# WicinskiPI.net
KiCad netlist of a schematic drawn in EAGLE
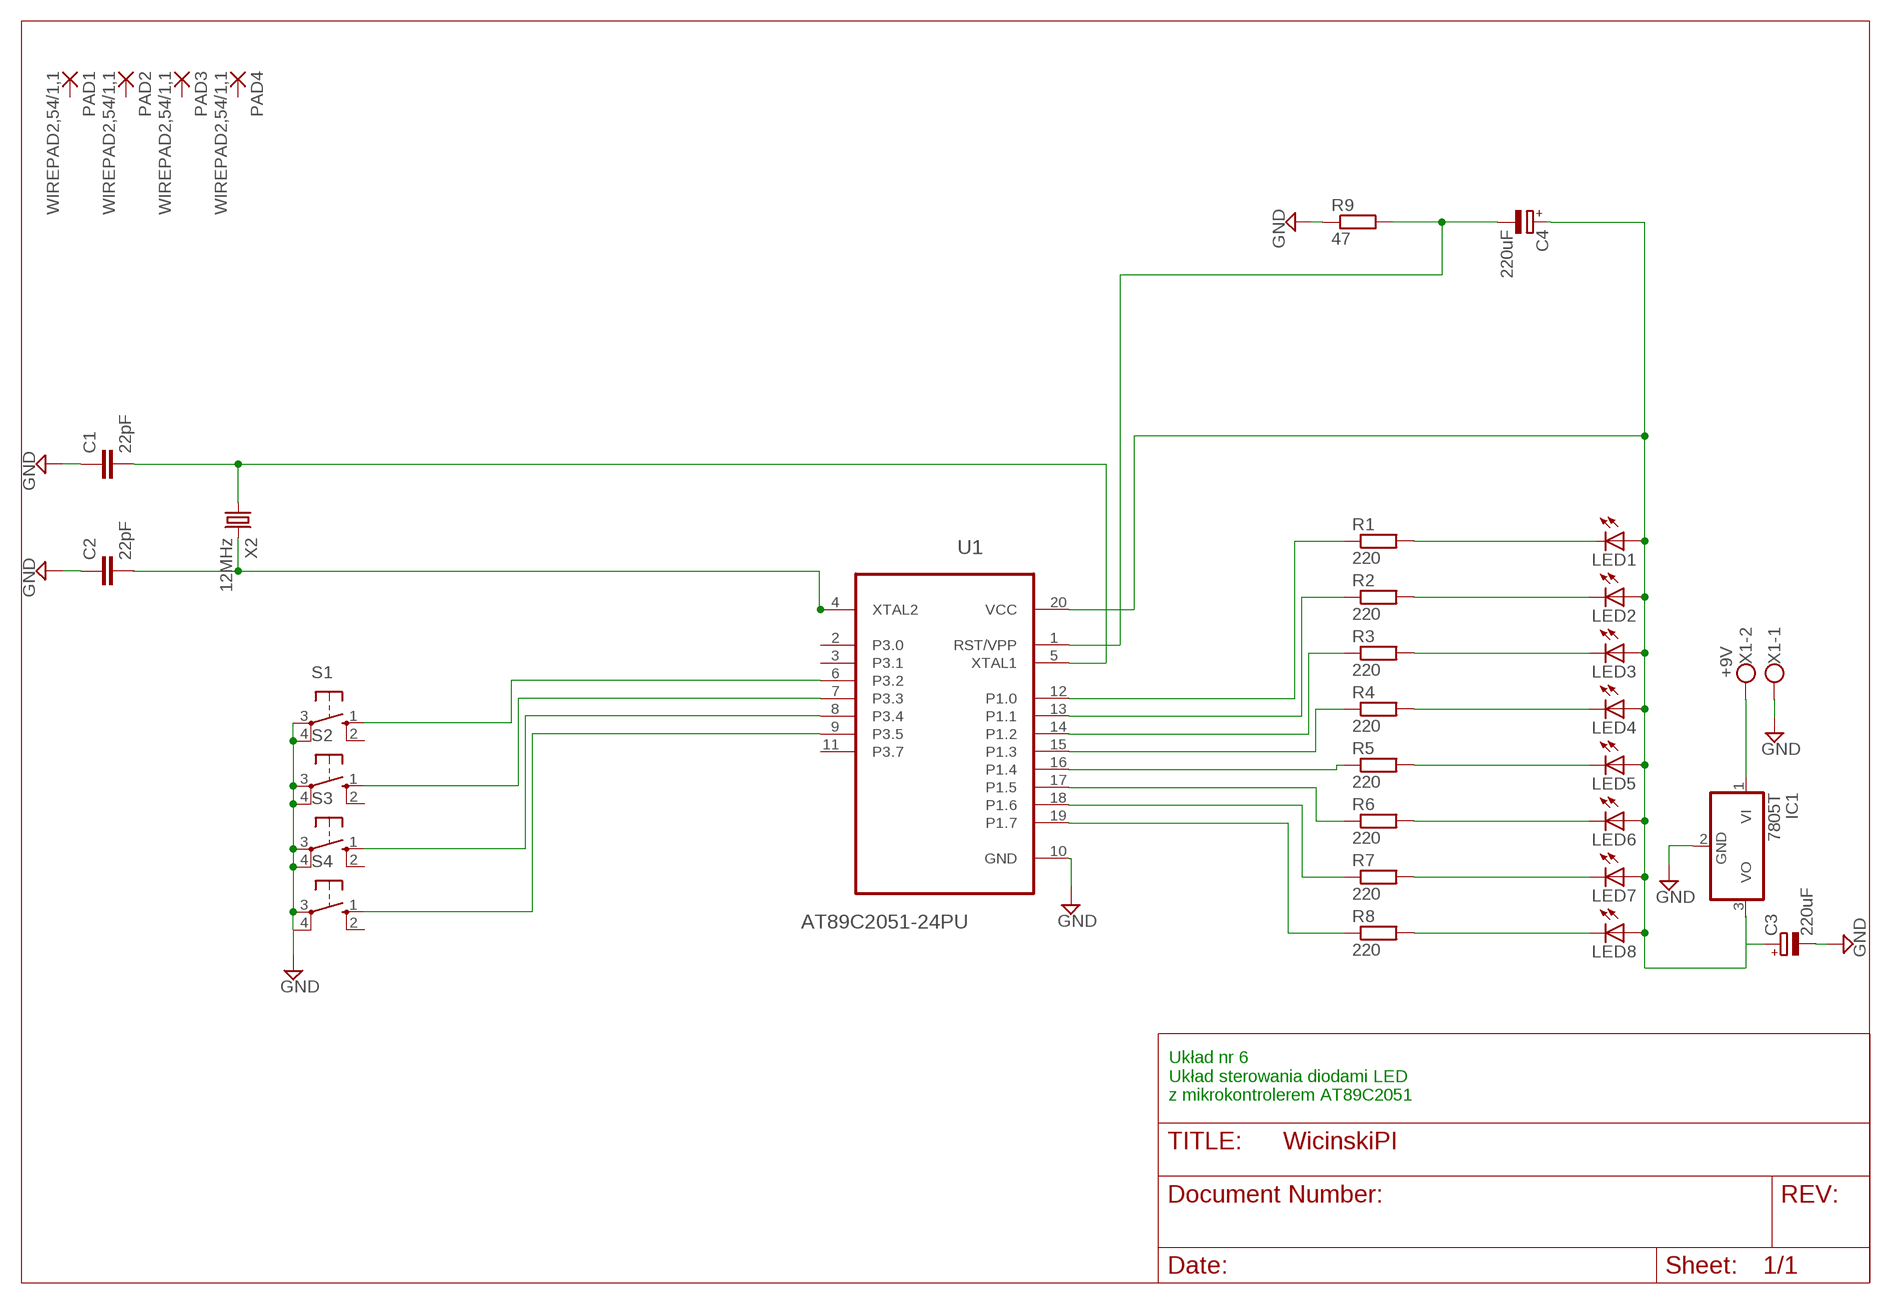
[diagram p0: schematic, sheet 1]

(export (version "E")
  (design (tool "Eeschema 10.0.6"))
  (components
    (comp (ref "C1")
      (value "22pF")
      (footprint "eagle-import:C1206")
      (libsource (lib "eagle-import") (part "C-EUC1206"))
    )
    (comp (ref "C2")
      (value "22pF")
      (footprint "eagle-import:C1206")
      (libsource (lib "eagle-import") (part "C-EUC1206"))
    )
    (comp (ref "C3")
      (value "220uF")
      (footprint "eagle-import:E3,5-8")
      (libsource (lib "eagle-import") (part "CPOL-EUE3.5-8"))
    )
    (comp (ref "C4")
      (value "220uF")
      (footprint "eagle-import:E3,5-8")
      (libsource (lib "eagle-import") (part "CPOL-EUE3.5-8"))
    )
    (comp (ref "IC1")
      (value "7805T")
      (footprint "eagle-import:TO220H")
      (libsource (lib "eagle-import") (part "78T05"))
    )
    (comp (ref "LED1")
      (value "LED3MM")
      (footprint "eagle-import:LED3MM")
      (libsource (lib "eagle-import") (part "LED3MM"))
    )
    (comp (ref "LED2")
      (value "LED3MM")
      (footprint "eagle-import:LED3MM")
      (libsource (lib "eagle-import") (part "LED3MM"))
    )
    (comp (ref "LED3")
      (value "LED3MM")
      (footprint "eagle-import:LED3MM")
      (libsource (lib "eagle-import") (part "LED3MM"))
    )
    (comp (ref "LED4")
      (value "LED3MM")
      (footprint "eagle-import:LED3MM")
      (libsource (lib "eagle-import") (part "LED3MM"))
    )
    (comp (ref "LED5")
      (value "LED3MM")
      (footprint "eagle-import:LED3MM")
      (libsource (lib "eagle-import") (part "LED3MM"))
    )
    (comp (ref "LED6")
      (value "LED3MM")
      (footprint "eagle-import:LED3MM")
      (libsource (lib "eagle-import") (part "LED3MM"))
    )
    (comp (ref "LED7")
      (value "LED3MM")
      (footprint "eagle-import:LED3MM")
      (libsource (lib "eagle-import") (part "LED3MM"))
    )
    (comp (ref "LED8")
      (value "LED3MM")
      (footprint "eagle-import:LED3MM")
      (libsource (lib "eagle-import") (part "LED3MM"))
    )
    (comp (ref "PAD1")
      (value "WIREPAD2,54/1,1")
      (footprint "eagle-import:2,54_1,1")
      (libsource (lib "eagle-import") (part "WIREPAD2,54/1,1"))
    )
    (comp (ref "PAD2")
      (value "WIREPAD2,54/1,1")
      (footprint "eagle-import:2,54_1,1")
      (libsource (lib "eagle-import") (part "WIREPAD2,54/1,1"))
    )
    (comp (ref "PAD3")
      (value "WIREPAD2,54/1,1")
      (footprint "eagle-import:2,54_1,1")
      (libsource (lib "eagle-import") (part "WIREPAD2,54/1,1"))
    )
    (comp (ref "PAD4")
      (value "WIREPAD2,54/1,1")
      (footprint "eagle-import:2,54_1,1")
      (libsource (lib "eagle-import") (part "WIREPAD2,54/1,1"))
    )
    (comp (ref "R1")
      (value "220")
      (footprint "eagle-import:R2012")
      (libsource (lib "eagle-import") (part "R-EU_R2012"))
    )
    (comp (ref "R2")
      (value "220")
      (footprint "eagle-import:R2012")
      (libsource (lib "eagle-import") (part "R-EU_R2012"))
    )
    (comp (ref "R3")
      (value "220")
      (footprint "eagle-import:R2012")
      (libsource (lib "eagle-import") (part "R-EU_R2012"))
    )
    (comp (ref "R4")
      (value "220")
      (footprint "eagle-import:R2012")
      (libsource (lib "eagle-import") (part "R-EU_R2012"))
    )
    (comp (ref "R5")
      (value "220")
      (footprint "eagle-import:R2012")
      (libsource (lib "eagle-import") (part "R-EU_R2012"))
    )
    (comp (ref "R6")
      (value "220")
      (footprint "eagle-import:R2012")
      (libsource (lib "eagle-import") (part "R-EU_R2012"))
    )
    (comp (ref "R7")
      (value "220")
      (footprint "eagle-import:R2012")
      (libsource (lib "eagle-import") (part "R-EU_R2012"))
    )
    (comp (ref "R8")
      (value "220")
      (footprint "eagle-import:R2012")
      (libsource (lib "eagle-import") (part "R-EU_R2012"))
    )
    (comp (ref "R9")
      (value "47")
      (footprint "eagle-import:R2012")
      (libsource (lib "eagle-import") (part "R-EU_R2012"))
    )
    (comp (ref "S1")
      (value "10-XX")
      (footprint "eagle-import:B3F-10XX")
      (fields (field (name "MPN") "B3F-1000"))
      (libsource (lib "eagle-import") (part "10-XX"))
    )
    (comp (ref "S2")
      (value "10-XX")
      (footprint "eagle-import:B3F-10XX")
      (fields (field (name "MPN") "B3F-1000"))
      (libsource (lib "eagle-import") (part "10-XX"))
    )
    (comp (ref "S3")
      (value "10-XX")
      (footprint "eagle-import:B3F-10XX")
      (fields (field (name "MPN") "B3F-1000"))
      (libsource (lib "eagle-import") (part "10-XX"))
    )
    (comp (ref "S4")
      (value "10-XX")
      (footprint "eagle-import:B3F-10XX")
      (fields (field (name "MPN") "B3F-1000"))
      (libsource (lib "eagle-import") (part "10-XX"))
    )
    (comp (ref "U1")
      (value "AT89C2051-24PU")
      (footprint "eagle-import:DIP254P762X533-20")
      (fields (field (name "MF") "Microchip"))
      (libsource (lib "eagle-import") (part "AT89C2051-24PU"))
    )
    (comp (ref "X1")
      (value "+9V")
      (footprint "eagle-import:W237-102")
      (fields (field (name "MPN") "237-102"))
      (libsource (lib "eagle-import") (part "W237-102"))
    )
    (comp (ref "X2")
      (value "12MHz")
      (footprint "eagle-import:HC49")
      (libsource (lib "eagle-import") (part "CRYSTALS-NOGND-HC49"))
    )
  )
  (nets
    (net (code "1") (name "GND") (class "Default")
      (node (ref "C1") (pin "1") (pinfunction "1_1") (pintype "passive"))
      (node (ref "C2") (pin "1") (pinfunction "1_1") (pintype "passive"))
      (node (ref "C3") (pin "-") (pinfunction "-_-") (pintype "passive"))
      (node (ref "IC1") (pin "2") (pinfunction "GND_2") (pintype "passive"))
      (node (ref "R9") (pin "1") (pinfunction "1_1") (pintype "passive"))
      (node (ref "S1") (pin "3") (pinfunction "P_3") (pintype "passive"))
      (node (ref "S1") (pin "4") (pinfunction "P1_4") (pintype "passive"))
      (node (ref "S2") (pin "3") (pinfunction "P_3") (pintype "passive"))
      (node (ref "S2") (pin "4") (pinfunction "P1_4") (pintype "passive"))
      (node (ref "S3") (pin "3") (pinfunction "P_3") (pintype "passive"))
      (node (ref "S3") (pin "4") (pinfunction "P1_4") (pintype "passive"))
      (node (ref "S4") (pin "3") (pinfunction "P_3") (pintype "passive"))
      (node (ref "S4") (pin "4") (pinfunction "P1_4") (pintype "passive"))
      (node (ref "U1") (pin "10") (pinfunction "GND_10") (pintype "passive"))
      (node (ref "X1") (pin "1") (pinfunction "KL_1") (pintype "passive"))
    )
    (net (code "2") (name "Net-(IC1-VI)") (class "Default")
      (node (ref "IC1") (pin "1") (pinfunction "VI_1") (pintype "input"))
      (node (ref "X1") (pin "2") (pinfunction "KL_2") (pintype "passive"))
    )
    (net (code "3") (name "Net-(IC1-VO)") (class "Default")
      (node (ref "C3") (pin "+") (pinfunction "+_+") (pintype "passive"))
      (node (ref "C4") (pin "+") (pinfunction "+_+") (pintype "passive"))
      (node (ref "IC1") (pin "3") (pinfunction "VO_3") (pintype "passive"))
      (node (ref "LED1") (pin "A") (pinfunction "A_A") (pintype "passive"))
      (node (ref "LED2") (pin "A") (pinfunction "A_A") (pintype "passive"))
      (node (ref "LED3") (pin "A") (pinfunction "A_A") (pintype "passive"))
      (node (ref "LED4") (pin "A") (pinfunction "A_A") (pintype "passive"))
      (node (ref "LED5") (pin "A") (pinfunction "A_A") (pintype "passive"))
      (node (ref "LED6") (pin "A") (pinfunction "A_A") (pintype "passive"))
      (node (ref "LED7") (pin "A") (pinfunction "A_A") (pintype "passive"))
      (node (ref "LED8") (pin "A") (pinfunction "A_A") (pintype "passive"))
      (node (ref "U1") (pin "20") (pinfunction "VCC_20") (pintype "power_in"))
    )
    (net (code "4") (name "Net-(LED1-C)") (class "Default")
      (node (ref "LED1") (pin "K") (pinfunction "C_K") (pintype "passive"))
      (node (ref "R1") (pin "2") (pinfunction "2_2") (pintype "passive"))
    )
    (net (code "5") (name "Net-(LED2-C)") (class "Default")
      (node (ref "LED2") (pin "K") (pinfunction "C_K") (pintype "passive"))
      (node (ref "R2") (pin "2") (pinfunction "2_2") (pintype "passive"))
    )
    (net (code "6") (name "Net-(LED3-C)") (class "Default")
      (node (ref "LED3") (pin "K") (pinfunction "C_K") (pintype "passive"))
      (node (ref "R3") (pin "2") (pinfunction "2_2") (pintype "passive"))
    )
    (net (code "7") (name "Net-(LED4-C)") (class "Default")
      (node (ref "LED4") (pin "K") (pinfunction "C_K") (pintype "passive"))
      (node (ref "R4") (pin "2") (pinfunction "2_2") (pintype "passive"))
    )
    (net (code "8") (name "Net-(LED5-C)") (class "Default")
      (node (ref "LED5") (pin "K") (pinfunction "C_K") (pintype "passive"))
      (node (ref "R5") (pin "2") (pinfunction "2_2") (pintype "passive"))
    )
    (net (code "9") (name "Net-(LED6-C)") (class "Default")
      (node (ref "LED6") (pin "K") (pinfunction "C_K") (pintype "passive"))
      (node (ref "R6") (pin "2") (pinfunction "2_2") (pintype "passive"))
    )
    (net (code "10") (name "Net-(LED7-C)") (class "Default")
      (node (ref "LED7") (pin "K") (pinfunction "C_K") (pintype "passive"))
      (node (ref "R7") (pin "2") (pinfunction "2_2") (pintype "passive"))
    )
    (net (code "11") (name "Net-(LED8-C)") (class "Default")
      (node (ref "LED8") (pin "K") (pinfunction "C_K") (pintype "passive"))
      (node (ref "R8") (pin "2") (pinfunction "2_2") (pintype "passive"))
    )
    (net (code "12") (name "Net-(S1-S)") (class "Default")
      (node (ref "S1") (pin "1") (pinfunction "S_1") (pintype "passive"))
      (node (ref "U1") (pin "6") (pinfunction "P3.2_6") (pintype "bidirectional"))
    )
    (net (code "13") (name "Net-(S2-S)") (class "Default")
      (node (ref "S2") (pin "1") (pinfunction "S_1") (pintype "passive"))
      (node (ref "U1") (pin "7") (pinfunction "P3.3_7") (pintype "bidirectional"))
    )
    (net (code "14") (name "Net-(S3-S)") (class "Default")
      (node (ref "S3") (pin "1") (pinfunction "S_1") (pintype "passive"))
      (node (ref "U1") (pin "8") (pinfunction "P3.4_8") (pintype "bidirectional"))
    )
    (net (code "15") (name "Net-(S4-S)") (class "Default")
      (node (ref "S4") (pin "1") (pinfunction "S_1") (pintype "passive"))
      (node (ref "U1") (pin "9") (pinfunction "P3.5_9") (pintype "bidirectional"))
    )
    (net (code "16") (name "Net-(U1-P1.0)") (class "Default")
      (node (ref "R1") (pin "1") (pinfunction "1_1") (pintype "passive"))
      (node (ref "U1") (pin "12") (pinfunction "P1.0_12") (pintype "bidirectional"))
    )
    (net (code "17") (name "Net-(U1-P1.1)") (class "Default")
      (node (ref "R2") (pin "1") (pinfunction "1_1") (pintype "passive"))
      (node (ref "U1") (pin "13") (pinfunction "P1.1_13") (pintype "bidirectional"))
    )
    (net (code "18") (name "Net-(U1-P1.2)") (class "Default")
      (node (ref "R3") (pin "1") (pinfunction "1_1") (pintype "passive"))
      (node (ref "U1") (pin "14") (pinfunction "P1.2_14") (pintype "bidirectional"))
    )
    (net (code "19") (name "Net-(U1-P1.3)") (class "Default")
      (node (ref "R4") (pin "1") (pinfunction "1_1") (pintype "passive"))
      (node (ref "U1") (pin "15") (pinfunction "P1.3_15") (pintype "bidirectional"))
    )
    (net (code "20") (name "Net-(U1-P1.4)") (class "Default")
      (node (ref "R5") (pin "1") (pinfunction "1_1") (pintype "passive"))
      (node (ref "U1") (pin "16") (pinfunction "P1.4_16") (pintype "bidirectional"))
    )
    (net (code "21") (name "Net-(U1-P1.5)") (class "Default")
      (node (ref "R6") (pin "1") (pinfunction "1_1") (pintype "passive"))
      (node (ref "U1") (pin "17") (pinfunction "P1.5_17") (pintype "bidirectional"))
    )
    (net (code "22") (name "Net-(U1-P1.6)") (class "Default")
      (node (ref "R7") (pin "1") (pinfunction "1_1") (pintype "passive"))
      (node (ref "U1") (pin "18") (pinfunction "P1.6_18") (pintype "bidirectional"))
    )
    (net (code "23") (name "Net-(U1-P1.7)") (class "Default")
      (node (ref "R8") (pin "1") (pinfunction "1_1") (pintype "passive"))
      (node (ref "U1") (pin "19") (pinfunction "P1.7_19") (pintype "bidirectional"))
    )
    (net (code "24") (name "Net-(U1-RST{slash}VPP)") (class "Default")
      (node (ref "C4") (pin "-") (pinfunction "-_-") (pintype "passive"))
      (node (ref "R9") (pin "2") (pinfunction "2_2") (pintype "passive"))
      (node (ref "U1") (pin "1") (pinfunction "RST/VPP_1") (pintype "input"))
    )
    (net (code "25") (name "Net-(U1-XTAL1)") (class "Default")
      (node (ref "C1") (pin "2") (pinfunction "2_2") (pintype "passive"))
      (node (ref "U1") (pin "5") (pinfunction "XTAL1_5") (pintype "input"))
      (node (ref "X2") (pin "1") (pinfunction "1_1") (pintype "passive"))
    )
    (net (code "26") (name "Net-(U1-XTAL2)") (class "Default")
      (node (ref "C2") (pin "2") (pinfunction "2_2") (pintype "passive"))
      (node (ref "U1") (pin "4") (pinfunction "XTAL2_4") (pintype "output"))
      (node (ref "X2") (pin "2") (pinfunction "2_2") (pintype "passive"))
    )
    (net (code "27") (name "unconnected-(PAD1-P-Pad1)") (class "Default")
      (node (ref "PAD1") (pin "1") (pinfunction "P_1") (pintype "passive"))
    )
    (net (code "28") (name "unconnected-(PAD2-P-Pad1)") (class "Default")
      (node (ref "PAD2") (pin "1") (pinfunction "P_1") (pintype "passive"))
    )
    (net (code "29") (name "unconnected-(PAD3-P-Pad1)") (class "Default")
      (node (ref "PAD3") (pin "1") (pinfunction "P_1") (pintype "passive"))
    )
    (net (code "30") (name "unconnected-(PAD4-P-Pad1)") (class "Default")
      (node (ref "PAD4") (pin "1") (pinfunction "P_1") (pintype "passive"))
    )
    (net (code "31") (name "unconnected-(S1-S1-Pad2)") (class "Default")
      (node (ref "S1") (pin "2") (pinfunction "S1_2") (pintype "passive"))
    )
    (net (code "32") (name "unconnected-(S2-S1-Pad2)") (class "Default")
      (node (ref "S2") (pin "2") (pinfunction "S1_2") (pintype "passive"))
    )
    (net (code "33") (name "unconnected-(S3-S1-Pad2)") (class "Default")
      (node (ref "S3") (pin "2") (pinfunction "S1_2") (pintype "passive"))
    )
    (net (code "34") (name "unconnected-(S4-S1-Pad2)") (class "Default")
      (node (ref "S4") (pin "2") (pinfunction "S1_2") (pintype "passive"))
    )
    (net (code "35") (name "unconnected-(U1-P3.0-Pad2)") (class "Default")
      (node (ref "U1") (pin "2") (pinfunction "P3.0_2") (pintype "bidirectional"))
    )
    (net (code "36") (name "unconnected-(U1-P3.1-Pad3)") (class "Default")
      (node (ref "U1") (pin "3") (pinfunction "P3.1_3") (pintype "bidirectional"))
    )
    (net (code "37") (name "unconnected-(U1-P3.7-Pad11)") (class "Default")
      (node (ref "U1") (pin "11") (pinfunction "P3.7_11") (pintype "bidirectional"))
    )
  )
)
